# 9xVoice_MikeB_SMD_v1_0.net
KiCad netlist of a schematic drawn in EAGLE
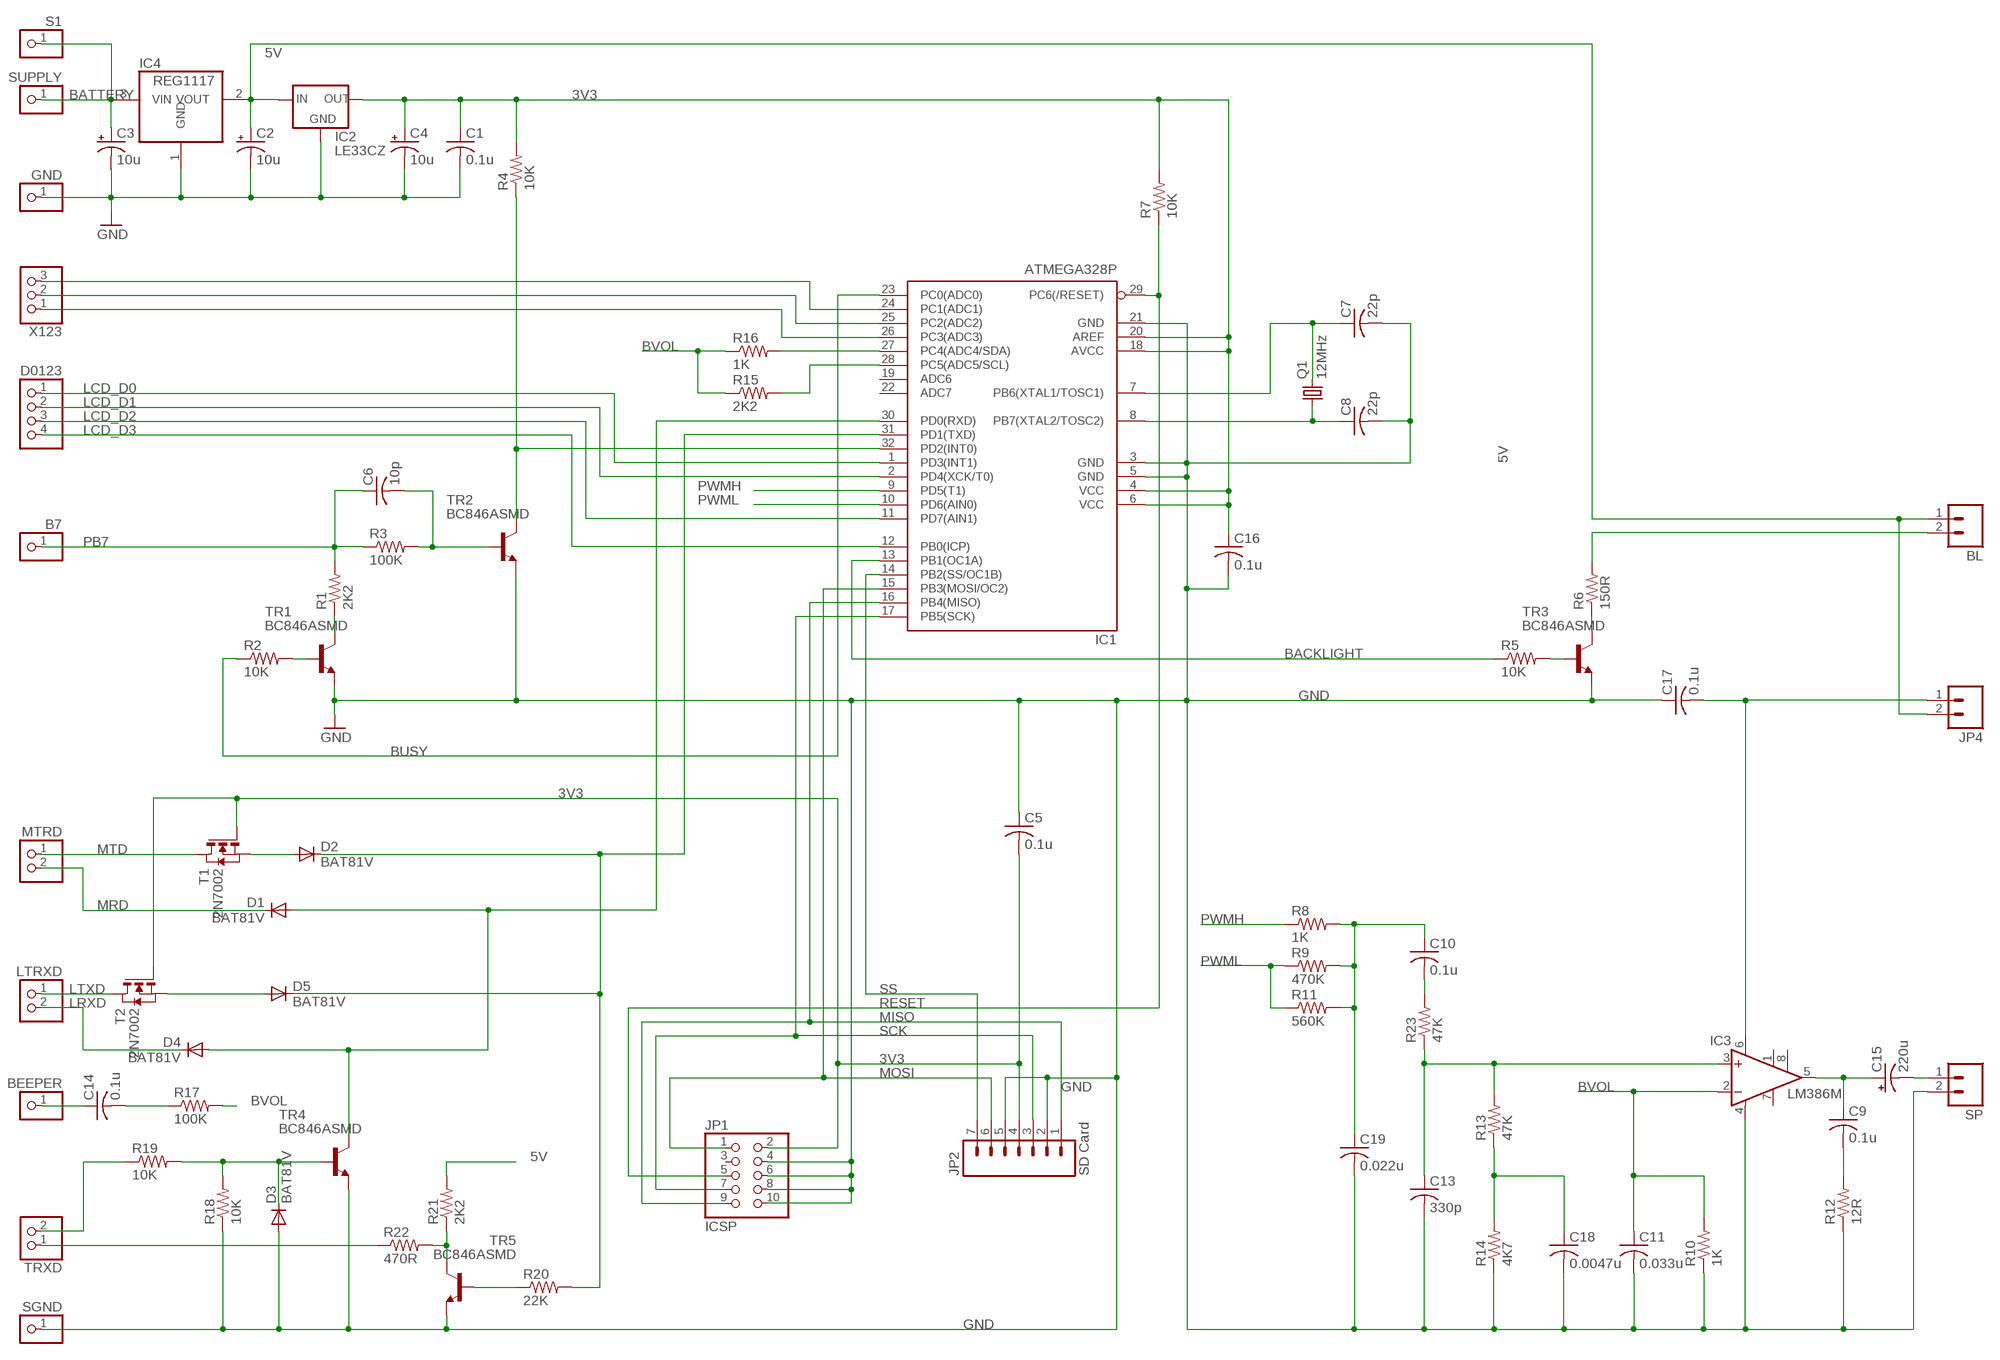
[diagram p0: schematic, sheet 1]

(export (version "E")
  (design (tool "Eeschema 10.0.6"))
  (components
    (comp (ref "B7")
      (value "PINHD-1X1")
      (footprint "eagle-import:1X01")
      (libsource (lib "eagle-import") (part "PINHD-1X1"))
    )
    (comp (ref "BEEPER")
      (value "PINHD-1X1")
      (footprint "eagle-import:1X01")
      (libsource (lib "eagle-import") (part "PINHD-1X1"))
    )
    (comp (ref "BL")
      (value "M02PTH")
      (footprint "eagle-import:1X02")
      (libsource (lib "eagle-import") (part "M02PTH"))
    )
    (comp (ref "C1")
      (value "0.1u")
      (footprint "eagle-import:C1206")
      (libsource (lib "eagle-import") (part "C-USC1206"))
    )
    (comp (ref "C2")
      (value "10u")
      (footprint "eagle-import:A_3216-18R")
      (libsource (lib "eagle-import") (part "CPOL-USA/3216-18R"))
    )
    (comp (ref "C3")
      (value "10u")
      (footprint "eagle-import:A_3216-18R")
      (libsource (lib "eagle-import") (part "CPOL-USA/3216-18R"))
    )
    (comp (ref "C4")
      (value "10u")
      (footprint "eagle-import:A_3216-18R")
      (libsource (lib "eagle-import") (part "CPOL-USA/3216-18R"))
    )
    (comp (ref "C5")
      (value "0.1u")
      (footprint "eagle-import:C1206")
      (libsource (lib "eagle-import") (part "C-USC1206"))
    )
    (comp (ref "C6")
      (value "10p")
      (footprint "eagle-import:C1206")
      (libsource (lib "eagle-import") (part "C-USC1206"))
    )
    (comp (ref "C7")
      (value "22p")
      (footprint "eagle-import:C1206")
      (libsource (lib "eagle-import") (part "C-USC1206"))
    )
    (comp (ref "C8")
      (value "22p")
      (footprint "eagle-import:C1206")
      (libsource (lib "eagle-import") (part "C-USC1206"))
    )
    (comp (ref "C9")
      (value "0.1u")
      (footprint "eagle-import:C1206")
      (libsource (lib "eagle-import") (part "C-USC1206"))
    )
    (comp (ref "C10")
      (value "0.1u")
      (footprint "eagle-import:C1206")
      (libsource (lib "eagle-import") (part "C-USC1206"))
    )
    (comp (ref "C11")
      (value "0.033u")
      (footprint "eagle-import:C1206")
      (libsource (lib "eagle-import") (part "C-USC1206"))
    )
    (comp (ref "C13")
      (value "330p")
      (footprint "eagle-import:C1206")
      (libsource (lib "eagle-import") (part "C-USC1206"))
    )
    (comp (ref "C14")
      (value "0.1u")
      (footprint "eagle-import:C1206")
      (libsource (lib "eagle-import") (part "C-USC1206"))
    )
    (comp (ref "C15")
      (value "220u")
      (footprint "eagle-import:CT7343")
      (libsource (lib "eagle-import") (part "CPOL-USCT7343"))
    )
    (comp (ref "C16")
      (value "0.1u")
      (footprint "eagle-import:C1206")
      (libsource (lib "eagle-import") (part "C-USC1206"))
    )
    (comp (ref "C17")
      (value "0.1u")
      (footprint "eagle-import:C1206")
      (libsource (lib "eagle-import") (part "C-USC1206"))
    )
    (comp (ref "C18")
      (value "0.0047u")
      (footprint "eagle-import:C1206")
      (libsource (lib "eagle-import") (part "C-USC1206"))
    )
    (comp (ref "C19")
      (value "0.022u")
      (footprint "eagle-import:C1206")
      (libsource (lib "eagle-import") (part "C-USC1206"))
    )
    (comp (ref "D1")
      (value "BAT81V")
      (footprint "eagle-import:SOD123")
      (libsource (lib "eagle-import") (part "DIODE-SOD123"))
    )
    (comp (ref "D2")
      (value "BAT81V")
      (footprint "eagle-import:SOD123")
      (libsource (lib "eagle-import") (part "DIODE-SOD123"))
    )
    (comp (ref "D3")
      (value "BAT81V")
      (footprint "eagle-import:SOD123")
      (libsource (lib "eagle-import") (part "DIODE-SOD123"))
    )
    (comp (ref "D4")
      (value "BAT81V")
      (footprint "eagle-import:SOD123")
      (libsource (lib "eagle-import") (part "DIODE-SOD123"))
    )
    (comp (ref "D5")
      (value "BAT81V")
      (footprint "eagle-import:SOD123")
      (libsource (lib "eagle-import") (part "DIODE-SOD123"))
    )
    (comp (ref "D0123")
      (value "PINHD-1X4")
      (footprint "eagle-import:1X04")
      (libsource (lib "eagle-import") (part "PINHD-1X4"))
    )
    (comp (ref "GND")
      (value "PINHD-1X1")
      (footprint "eagle-import:1X01")
      (libsource (lib "eagle-import") (part "PINHD-1X1"))
    )
    (comp (ref "IC1")
      (value "ATMEGA328P")
      (footprint "eagle-import:TQFP32-08")
      (fields
        (field (name "MPN") "ATMEGA8-16AU")
        (field (name "MPN_1") "ATMEGA8-16AU")
        (field (name "OC_FARNELL") "9171371")
        (field (name "OC_NEWARK") "73M8863")
      )
      (libsource (lib "eagle-import") (part "MEGA8-AI"))
    )
    (comp (ref "IC2")
      (value "LE33CZ")
      (footprint "eagle-import:SOT23")
      (libsource (lib "eagle-import") (part "XC63FPM"))
    )
    (comp (ref "IC3")
      (value "LM386M")
      (footprint "eagle-import:SO08")
      (libsource (lib "eagle-import") (part "LM386?-M1"))
    )
    (comp (ref "IC4")
      (value "REG1117")
      (footprint "eagle-import:SOT223")
      (libsource (lib "eagle-import") (part "REG1117"))
    )
    (comp (ref "JP1")
      (value "ICSP")
      (footprint "eagle-import:2X05")
      (libsource (lib "eagle-import") (part "PINHD-2X5"))
    )
    (comp (ref "JP2")
      (value "SD Card")
      (footprint "eagle-import:1X07")
      (libsource (lib "eagle-import") (part "M07"))
    )
    (comp (ref "JP4")
      (value "M02PTH")
      (footprint "eagle-import:1X02")
      (libsource (lib "eagle-import") (part "M02PTH"))
    )
    (comp (ref "LTRXD")
      (value "PINHD-1X2")
      (footprint "eagle-import:1X02")
      (libsource (lib "eagle-import") (part "PINHD-1X2"))
    )
    (comp (ref "MTRD")
      (value "PINHD-1X2")
      (footprint "eagle-import:1X02")
      (libsource (lib "eagle-import") (part "PINHD-1X2"))
    )
    (comp (ref "Q1")
      (value "12MHz")
      (footprint "eagle-import:2-SMD")
      (libsource (lib "eagle-import") (part "7A"))
    )
    (comp (ref "R1")
      (value "2K2")
      (footprint "eagle-import:R1206")
      (libsource (lib "eagle-import") (part "R-US_R1206"))
    )
    (comp (ref "R2")
      (value "10K")
      (footprint "eagle-import:R1206")
      (libsource (lib "eagle-import") (part "R-US_R1206"))
    )
    (comp (ref "R3")
      (value "100K")
      (footprint "eagle-import:R1206")
      (libsource (lib "eagle-import") (part "R-US_R1206"))
    )
    (comp (ref "R4")
      (value "10K")
      (footprint "eagle-import:R1206")
      (libsource (lib "eagle-import") (part "R-US_R1206"))
    )
    (comp (ref "R5")
      (value "10K")
      (footprint "eagle-import:R1206")
      (libsource (lib "eagle-import") (part "R-US_R1206"))
    )
    (comp (ref "R6")
      (value "150R")
      (footprint "eagle-import:R1206")
      (libsource (lib "eagle-import") (part "R-US_R1206"))
    )
    (comp (ref "R7")
      (value "10K")
      (footprint "eagle-import:R1206")
      (libsource (lib "eagle-import") (part "R-US_R1206"))
    )
    (comp (ref "R8")
      (value "1K")
      (footprint "eagle-import:R1206")
      (libsource (lib "eagle-import") (part "R-US_R1206"))
    )
    (comp (ref "R9")
      (value "470K")
      (footprint "eagle-import:R1206")
      (libsource (lib "eagle-import") (part "R-US_R1206"))
    )
    (comp (ref "R10")
      (value "1K")
      (footprint "eagle-import:R1206")
      (libsource (lib "eagle-import") (part "R-US_R1206"))
    )
    (comp (ref "R11")
      (value "560K")
      (footprint "eagle-import:R1206")
      (libsource (lib "eagle-import") (part "R-US_R1206"))
    )
    (comp (ref "R12")
      (value "12R")
      (footprint "eagle-import:R1206")
      (libsource (lib "eagle-import") (part "R-US_R1206"))
    )
    (comp (ref "R13")
      (value "47K")
      (footprint "eagle-import:R1206")
      (libsource (lib "eagle-import") (part "R-US_R1206"))
    )
    (comp (ref "R14")
      (value "4K7")
      (footprint "eagle-import:R1206")
      (libsource (lib "eagle-import") (part "R-US_R1206"))
    )
    (comp (ref "R15")
      (value "2K2")
      (footprint "eagle-import:R1206")
      (libsource (lib "eagle-import") (part "R-US_R1206"))
    )
    (comp (ref "R16")
      (value "1K")
      (footprint "eagle-import:R1206")
      (libsource (lib "eagle-import") (part "R-US_R1206"))
    )
    (comp (ref "R17")
      (value "100K")
      (footprint "eagle-import:R1206")
      (libsource (lib "eagle-import") (part "R-US_R1206"))
    )
    (comp (ref "R18")
      (value "10K")
      (footprint "eagle-import:R1206")
      (libsource (lib "eagle-import") (part "R-US_R1206"))
    )
    (comp (ref "R19")
      (value "10K")
      (footprint "eagle-import:R1206")
      (libsource (lib "eagle-import") (part "R-US_R1206"))
    )
    (comp (ref "R20")
      (value "22K")
      (footprint "eagle-import:R1206")
      (libsource (lib "eagle-import") (part "R-US_R1206"))
    )
    (comp (ref "R21")
      (value "2K2")
      (footprint "eagle-import:R1206")
      (libsource (lib "eagle-import") (part "R-US_R1206"))
    )
    (comp (ref "R22")
      (value "470R")
      (footprint "eagle-import:R1206")
      (libsource (lib "eagle-import") (part "R-US_R1206"))
    )
    (comp (ref "R23")
      (value "47K")
      (footprint "eagle-import:R1206")
      (libsource (lib "eagle-import") (part "R-US_R1206"))
    )
    (comp (ref "S1")
      (value "PINHD-1X1")
      (footprint "eagle-import:1X01")
      (libsource (lib "eagle-import") (part "PINHD-1X1"))
    )
    (comp (ref "SGND")
      (value "PINHD-1X1")
      (footprint "eagle-import:1X01")
      (libsource (lib "eagle-import") (part "PINHD-1X1"))
    )
    (comp (ref "SP")
      (value "M02PTH")
      (footprint "eagle-import:1X02")
      (libsource (lib "eagle-import") (part "M02PTH"))
    )
    (comp (ref "SUPPLY")
      (value "PINHD-1X1")
      (footprint "eagle-import:1X01")
      (libsource (lib "eagle-import") (part "PINHD-1X1"))
    )
    (comp (ref "T1")
      (value "2N7002")
      (footprint "eagle-import:SOT-23")
      (libsource (lib "eagle-import") (part "NMOSSOT23"))
    )
    (comp (ref "T2")
      (value "2N7002")
      (footprint "eagle-import:SOT-23")
      (libsource (lib "eagle-import") (part "NMOSSOT23"))
    )
    (comp (ref "TR1")
      (value "BC846ASMD")
      (footprint "eagle-import:SOT23")
      (libsource (lib "eagle-import") (part "BC846SMDA"))
    )
    (comp (ref "TR2")
      (value "BC846ASMD")
      (footprint "eagle-import:SOT23")
      (libsource (lib "eagle-import") (part "BC846SMDA"))
    )
    (comp (ref "TR3")
      (value "BC846ASMD")
      (footprint "eagle-import:SOT23")
      (libsource (lib "eagle-import") (part "BC846SMDA"))
    )
    (comp (ref "TR4")
      (value "BC846ASMD")
      (footprint "eagle-import:SOT23")
      (libsource (lib "eagle-import") (part "BC846SMDA"))
    )
    (comp (ref "TR5")
      (value "BC846ASMD")
      (footprint "eagle-import:SOT23")
      (libsource (lib "eagle-import") (part "BC846SMDA"))
    )
    (comp (ref "TRXD")
      (value "PINHD-1X2")
      (footprint "eagle-import:1X02")
      (libsource (lib "eagle-import") (part "PINHD-1X2"))
    )
    (comp (ref "X123")
      (value "PINHD-1X3")
      (footprint "eagle-import:1X03")
      (libsource (lib "eagle-import") (part "PINHD-1X3"))
    )
  )
  (nets
    (net (code "1") (name "/3V3") (class "Default")
      (node (ref "C1") (pin "1") (pinfunction "1_1") (pintype "passive"))
      (node (ref "C16") (pin "1") (pinfunction "1_1") (pintype "passive"))
      (node (ref "C4") (pin "+") (pinfunction "+_+") (pintype "passive"))
      (node (ref "C5") (pin "2") (pinfunction "2_2") (pintype "passive"))
      (node (ref "IC1") (pin "18") (pinfunction "AVCC_18") (pintype "power_in"))
      (node (ref "IC1") (pin "20") (pinfunction "AREF_20") (pintype "passive"))
      (node (ref "IC1") (pin "4") (pinfunction "VCC_4") (pintype "power_in"))
      (node (ref "IC1") (pin "6") (pinfunction "VCC_6") (pintype "power_in"))
      (node (ref "IC2") (pin "2") (pinfunction "OUT_2") (pintype "passive"))
      (node (ref "JP1") (pin "2") (pinfunction "2_2") (pintype "passive"))
      (node (ref "JP2") (pin "4") (pinfunction "4_4") (pintype "passive"))
      (node (ref "R4") (pin "2") (pinfunction "2_2") (pintype "passive"))
      (node (ref "R7") (pin "2") (pinfunction "2_2") (pintype "passive"))
      (node (ref "T1") (pin "3") (pinfunction "G_3") (pintype "passive"))
      (node (ref "T2") (pin "3") (pinfunction "G_3") (pintype "passive"))
    )
    (net (code "2") (name "/5V") (class "Default")
      (node (ref "BL") (pin "1") (pinfunction "1_1") (pintype "passive"))
      (node (ref "C2") (pin "+") (pinfunction "+_+") (pintype "passive"))
      (node (ref "IC2") (pin "3") (pinfunction "IN_3") (pintype "input"))
      (node (ref "IC4") (pin "2") (pinfunction "VOUT_2") (pintype "output"))
      (node (ref "JP4") (pin "2") (pinfunction "2_2") (pintype "passive"))
      (node (ref "R21") (pin "2") (pinfunction "2_2") (pintype "passive"))
    )
    (net (code "3") (name "/BACKLIGHT") (class "Default")
      (node (ref "IC1") (pin "13") (pinfunction "PB1(OC1A)_13") (pintype "bidirectional"))
      (node (ref "R5") (pin "1") (pinfunction "1_1") (pintype "passive"))
    )
    (net (code "4") (name "/BATTERY") (class "Default")
      (node (ref "C3") (pin "+") (pinfunction "+_+") (pintype "passive"))
      (node (ref "IC4") (pin "3") (pinfunction "VIN_3") (pintype "input"))
      (node (ref "S1") (pin "1") (pinfunction "1_1") (pintype "passive"))
      (node (ref "SUPPLY") (pin "1") (pinfunction "1_1") (pintype "passive"))
    )
    (net (code "5") (name "/BUSY") (class "Default")
      (node (ref "IC1") (pin "23") (pinfunction "PC0(ADC0)_23") (pintype "bidirectional"))
      (node (ref "R2") (pin "1") (pinfunction "1_1") (pintype "passive"))
    )
    (net (code "6") (name "/BVOL") (class "Default")
      (node (ref "C11") (pin "1") (pinfunction "1_1") (pintype "passive"))
      (node (ref "IC3") (pin "2") (pinfunction "-IN_2") (pintype "input"))
      (node (ref "R10") (pin "2") (pinfunction "2_2") (pintype "passive"))
      (node (ref "R15") (pin "1") (pinfunction "1_1") (pintype "passive"))
      (node (ref "R16") (pin "1") (pinfunction "1_1") (pintype "passive"))
      (node (ref "R17") (pin "2") (pinfunction "2_2") (pintype "passive"))
    )
    (net (code "7") (name "/LCD_D0") (class "Default")
      (node (ref "D0123") (pin "1") (pinfunction "1_1") (pintype "passive"))
      (node (ref "IC1") (pin "1") (pinfunction "PD3(INT1)_1") (pintype "bidirectional"))
    )
    (net (code "8") (name "/LCD_D1") (class "Default")
      (node (ref "D0123") (pin "2") (pinfunction "2_2") (pintype "passive"))
      (node (ref "IC1") (pin "2") (pinfunction "PD4(XCK/T0)_2") (pintype "bidirectional"))
    )
    (net (code "9") (name "/LCD_D2") (class "Default")
      (node (ref "D0123") (pin "3") (pinfunction "3_3") (pintype "passive"))
      (node (ref "IC1") (pin "11") (pinfunction "PD7(AIN1)_11") (pintype "bidirectional"))
    )
    (net (code "10") (name "/LCD_D3") (class "Default")
      (node (ref "D0123") (pin "4") (pinfunction "4_4") (pintype "passive"))
      (node (ref "IC1") (pin "12") (pinfunction "PB0(ICP)_12") (pintype "bidirectional"))
    )
    (net (code "11") (name "/LRXD") (class "Default")
      (node (ref "D4") (pin "C") (pinfunction "C_C") (pintype "passive"))
      (node (ref "LTRXD") (pin "2") (pinfunction "2_2") (pintype "passive"))
    )
    (net (code "12") (name "/LTXD") (class "Default")
      (node (ref "LTRXD") (pin "1") (pinfunction "1_1") (pintype "passive"))
      (node (ref "T2") (pin "1") (pinfunction "D_1") (pintype "passive"))
    )
    (net (code "13") (name "/MISO") (class "Default")
      (node (ref "IC1") (pin "16") (pinfunction "PB4(MISO)_16") (pintype "bidirectional"))
      (node (ref "JP1") (pin "9") (pinfunction "9_9") (pintype "passive"))
      (node (ref "JP2") (pin "1") (pinfunction "1_1") (pintype "passive"))
    )
    (net (code "14") (name "/MOSI") (class "Default")
      (node (ref "IC1") (pin "15") (pinfunction "PB3(MOSI/OC2)_15") (pintype "bidirectional"))
      (node (ref "JP1") (pin "1") (pinfunction "1_1") (pintype "passive"))
      (node (ref "JP2") (pin "6") (pinfunction "6_6") (pintype "passive"))
    )
    (net (code "15") (name "/MRD") (class "Default")
      (node (ref "D1") (pin "C") (pinfunction "C_C") (pintype "passive"))
      (node (ref "MTRD") (pin "2") (pinfunction "2_2") (pintype "passive"))
    )
    (net (code "16") (name "/MTD") (class "Default")
      (node (ref "MTRD") (pin "1") (pinfunction "1_1") (pintype "passive"))
      (node (ref "T1") (pin "1") (pinfunction "D_1") (pintype "passive"))
    )
    (net (code "17") (name "/PB7") (class "Default")
      (node (ref "B7") (pin "1") (pinfunction "1_1") (pintype "passive"))
      (node (ref "C6") (pin "1") (pinfunction "1_1") (pintype "passive"))
      (node (ref "R1") (pin "2") (pinfunction "2_2") (pintype "passive"))
      (node (ref "R3") (pin "1") (pinfunction "1_1") (pintype "passive"))
    )
    (net (code "18") (name "/PWMH") (class "Default")
      (node (ref "IC1") (pin "9") (pinfunction "PD5(T1)_9") (pintype "bidirectional"))
      (node (ref "R8") (pin "1") (pinfunction "1_1") (pintype "passive"))
    )
    (net (code "19") (name "/PWML") (class "Default")
      (node (ref "IC1") (pin "10") (pinfunction "PD6(AIN0)_10") (pintype "bidirectional"))
      (node (ref "R11") (pin "1") (pinfunction "1_1") (pintype "passive"))
      (node (ref "R9") (pin "1") (pinfunction "1_1") (pintype "passive"))
    )
    (net (code "20") (name "/RESET") (class "Default")
      (node (ref "IC1") (pin "29") (pinfunction "PC6(/RESET)_29") (pintype "bidirectional"))
      (node (ref "JP1") (pin "5") (pinfunction "5_5") (pintype "passive"))
      (node (ref "R7") (pin "1") (pinfunction "1_1") (pintype "passive"))
    )
    (net (code "21") (name "/SCK") (class "Default")
      (node (ref "IC1") (pin "17") (pinfunction "PB5(SCK)_17") (pintype "bidirectional"))
      (node (ref "JP1") (pin "7") (pinfunction "7_7") (pintype "passive"))
      (node (ref "JP2") (pin "3") (pinfunction "3_3") (pintype "passive"))
    )
    (net (code "22") (name "/SS") (class "Default")
      (node (ref "IC1") (pin "14") (pinfunction "PB2(SS/OC1B)_14") (pintype "bidirectional"))
      (node (ref "JP2") (pin "7") (pinfunction "7_7") (pintype "passive"))
    )
    (net (code "23") (name "GND") (class "Default")
      (node (ref "C1") (pin "2") (pinfunction "2_2") (pintype "passive"))
      (node (ref "C11") (pin "2") (pinfunction "2_2") (pintype "passive"))
      (node (ref "C13") (pin "2") (pinfunction "2_2") (pintype "passive"))
      (node (ref "C16") (pin "2") (pinfunction "2_2") (pintype "passive"))
      (node (ref "C17") (pin "1") (pinfunction "1_1") (pintype "passive"))
      (node (ref "C18") (pin "2") (pinfunction "2_2") (pintype "passive"))
      (node (ref "C19") (pin "2") (pinfunction "2_2") (pintype "passive"))
      (node (ref "C2") (pin "-") (pinfunction "-_-") (pintype "passive"))
      (node (ref "C3") (pin "-") (pinfunction "-_-") (pintype "passive"))
      (node (ref "C4") (pin "-") (pinfunction "-_-") (pintype "passive"))
      (node (ref "C5") (pin "1") (pinfunction "1_1") (pintype "passive"))
      (node (ref "C7") (pin "2") (pinfunction "2_2") (pintype "passive"))
      (node (ref "C8") (pin "2") (pinfunction "2_2") (pintype "passive"))
      (node (ref "D3") (pin "A") (pinfunction "A_A") (pintype "passive"))
      (node (ref "GND") (pin "1") (pinfunction "1_1") (pintype "passive"))
      (node (ref "IC1") (pin "21") (pinfunction "GND_21") (pintype "power_in"))
      (node (ref "IC1") (pin "3") (pinfunction "GND_3") (pintype "power_in"))
      (node (ref "IC1") (pin "5") (pinfunction "GND_5") (pintype "power_in"))
      (node (ref "IC2") (pin "1") (pinfunction "GND_1") (pintype "input"))
      (node (ref "IC3") (pin "4") (pinfunction "GND_4") (pintype "power_in"))
      (node (ref "IC4") (pin "1") (pinfunction "GND_1") (pintype "power_in"))
      (node (ref "JP1") (pin "10") (pinfunction "10_10") (pintype "passive"))
      (node (ref "JP1") (pin "4") (pinfunction "4_4") (pintype "passive"))
      (node (ref "JP1") (pin "6") (pinfunction "6_6") (pintype "passive"))
      (node (ref "JP1") (pin "8") (pinfunction "8_8") (pintype "passive"))
      (node (ref "JP2") (pin "2") (pinfunction "2_2") (pintype "passive"))
      (node (ref "JP2") (pin "5") (pinfunction "5_5") (pintype "passive"))
      (node (ref "R10") (pin "1") (pinfunction "1_1") (pintype "passive"))
      (node (ref "R12") (pin "1") (pinfunction "1_1") (pintype "passive"))
      (node (ref "R14") (pin "1") (pinfunction "1_1") (pintype "passive"))
      (node (ref "R18") (pin "1") (pinfunction "1_1") (pintype "passive"))
      (node (ref "SGND") (pin "1") (pinfunction "1_1") (pintype "passive"))
      (node (ref "SP") (pin "2") (pinfunction "2_2") (pintype "passive"))
      (node (ref "TR1") (pin "2") (pinfunction "E_2") (pintype "passive"))
      (node (ref "TR2") (pin "2") (pinfunction "E_2") (pintype "passive"))
      (node (ref "TR3") (pin "2") (pinfunction "E_2") (pintype "passive"))
      (node (ref "TR4") (pin "2") (pinfunction "E_2") (pintype "passive"))
      (node (ref "TR5") (pin "2") (pinfunction "E_2") (pintype "passive"))
    )
    (net (code "24") (name "Net-(BEEPER-Pad1)") (class "Default")
      (node (ref "BEEPER") (pin "1") (pinfunction "1_1") (pintype "passive"))
      (node (ref "C14") (pin "1") (pinfunction "1_1") (pintype "passive"))
    )
    (net (code "25") (name "Net-(BL-Pad2)") (class "Default")
      (node (ref "BL") (pin "2") (pinfunction "2_2") (pintype "passive"))
      (node (ref "R6") (pin "2") (pinfunction "2_2") (pintype "passive"))
    )
    (net (code "26") (name "Net-(C9-Pad2)") (class "Default")
      (node (ref "C9") (pin "2") (pinfunction "2_2") (pintype "passive"))
      (node (ref "R12") (pin "2") (pinfunction "2_2") (pintype "passive"))
    )
    (net (code "27") (name "Net-(C10-Pad1)") (class "Default")
      (node (ref "C10") (pin "1") (pinfunction "1_1") (pintype "passive"))
      (node (ref "C19") (pin "1") (pinfunction "1_1") (pintype "passive"))
      (node (ref "R11") (pin "2") (pinfunction "2_2") (pintype "passive"))
      (node (ref "R8") (pin "2") (pinfunction "2_2") (pintype "passive"))
      (node (ref "R9") (pin "2") (pinfunction "2_2") (pintype "passive"))
    )
    (net (code "28") (name "Net-(C10-Pad2)") (class "Default")
      (node (ref "C10") (pin "2") (pinfunction "2_2") (pintype "passive"))
      (node (ref "R23") (pin "2") (pinfunction "2_2") (pintype "passive"))
    )
    (net (code "29") (name "Net-(C14-Pad2)") (class "Default")
      (node (ref "C14") (pin "2") (pinfunction "2_2") (pintype "passive"))
      (node (ref "R17") (pin "1") (pinfunction "1_1") (pintype "passive"))
    )
    (net (code "30") (name "Net-(C15-Pad-)") (class "Default")
      (node (ref "C15") (pin "-") (pinfunction "-_-") (pintype "passive"))
      (node (ref "SP") (pin "1") (pinfunction "1_1") (pintype "passive"))
    )
    (net (code "31") (name "Net-(C18-Pad1)") (class "Default")
      (node (ref "C18") (pin "1") (pinfunction "1_1") (pintype "passive"))
      (node (ref "R13") (pin "1") (pinfunction "1_1") (pintype "passive"))
      (node (ref "R14") (pin "2") (pinfunction "2_2") (pintype "passive"))
    )
    (net (code "32") (name "Net-(IC1-PB6(XTAL1{slash}TOSC1))") (class "Default")
      (node (ref "C7") (pin "1") (pinfunction "1_1") (pintype "passive"))
      (node (ref "IC1") (pin "7") (pinfunction "PB6(XTAL1/TOSC1)_7") (pintype "bidirectional"))
      (node (ref "Q1") (pin "P$2") (pinfunction "2_P$2") (pintype "passive"))
    )
    (net (code "33") (name "Net-(IC1-PB7(XTAL2{slash}TOSC2))") (class "Default")
      (node (ref "C8") (pin "1") (pinfunction "1_1") (pintype "passive"))
      (node (ref "IC1") (pin "8") (pinfunction "PB7(XTAL2/TOSC2)_8") (pintype "bidirectional"))
      (node (ref "Q1") (pin "P$1") (pinfunction "1_P$1") (pintype "passive"))
    )
    (net (code "34") (name "Net-(IC1-PC1(ADC1))") (class "Default")
      (node (ref "IC1") (pin "24") (pinfunction "PC1(ADC1)_24") (pintype "bidirectional"))
      (node (ref "X123") (pin "3") (pinfunction "3_3") (pintype "passive"))
    )
    (net (code "35") (name "Net-(IC1-PC2(ADC2))") (class "Default")
      (node (ref "IC1") (pin "25") (pinfunction "PC2(ADC2)_25") (pintype "bidirectional"))
      (node (ref "X123") (pin "2") (pinfunction "2_2") (pintype "passive"))
    )
    (net (code "36") (name "Net-(IC1-PC3(ADC3))") (class "Default")
      (node (ref "IC1") (pin "26") (pinfunction "PC3(ADC3)_26") (pintype "bidirectional"))
      (node (ref "X123") (pin "1") (pinfunction "1_1") (pintype "passive"))
    )
    (net (code "37") (name "Net-(IC1-PC4(ADC4{slash}SDA))") (class "Default")
      (node (ref "IC1") (pin "27") (pinfunction "PC4(ADC4/SDA)_27") (pintype "bidirectional"))
      (node (ref "R16") (pin "2") (pinfunction "2_2") (pintype "passive"))
    )
    (net (code "38") (name "Net-(IC1-PC5(ADC5{slash}SCL))") (class "Default")
      (node (ref "IC1") (pin "28") (pinfunction "PC5(ADC5/SCL)_28") (pintype "bidirectional"))
      (node (ref "R15") (pin "2") (pinfunction "2_2") (pintype "passive"))
    )
    (net (code "39") (name "Net-(IC1-PD0(RXD))") (class "Default")
      (node (ref "D1") (pin "A") (pinfunction "A_A") (pintype "passive"))
      (node (ref "D4") (pin "A") (pinfunction "A_A") (pintype "passive"))
      (node (ref "IC1") (pin "30") (pinfunction "PD0(RXD)_30") (pintype "bidirectional"))
      (node (ref "TR4") (pin "3") (pinfunction "C_3") (pintype "passive"))
    )
    (net (code "40") (name "Net-(IC1-PD1(TXD))") (class "Default")
      (node (ref "D2") (pin "C") (pinfunction "C_C") (pintype "passive"))
      (node (ref "D5") (pin "C") (pinfunction "C_C") (pintype "passive"))
      (node (ref "IC1") (pin "31") (pinfunction "PD1(TXD)_31") (pintype "bidirectional"))
      (node (ref "R20") (pin "2") (pinfunction "2_2") (pintype "passive"))
    )
    (net (code "41") (name "Net-(IC1-PD2(INT0))") (class "Default")
      (node (ref "IC1") (pin "32") (pinfunction "PD2(INT0)_32") (pintype "bidirectional"))
      (node (ref "R4") (pin "1") (pinfunction "1_1") (pintype "passive"))
      (node (ref "TR2") (pin "3") (pinfunction "C_3") (pintype "passive"))
    )
    (net (code "42") (name "Net-(IC3-+IN)") (class "Default")
      (node (ref "C13") (pin "1") (pinfunction "1_1") (pintype "passive"))
      (node (ref "IC3") (pin "3") (pinfunction "+IN_3") (pintype "input"))
      (node (ref "R13") (pin "2") (pinfunction "2_2") (pintype "passive"))
      (node (ref "R23") (pin "1") (pinfunction "1_1") (pintype "passive"))
    )
    (net (code "43") (name "Net-(IC3-OUT)") (class "Default")
      (node (ref "C15") (pin "+") (pinfunction "+_+") (pintype "passive"))
      (node (ref "C9") (pin "1") (pinfunction "1_1") (pintype "passive"))
      (node (ref "IC3") (pin "5") (pinfunction "OUT_5") (pintype "output"))
    )
    (net (code "44") (name "Net-(IC3-VS)") (class "Default")
      (node (ref "C17") (pin "2") (pinfunction "2_2") (pintype "passive"))
      (node (ref "IC3") (pin "6") (pinfunction "VS_6") (pintype "power_in"))
      (node (ref "JP4") (pin "1") (pinfunction "1_1") (pintype "passive"))
    )
    (net (code "45") (name "Net-(R19-Pad1)") (class "Default")
      (node (ref "R19") (pin "1") (pinfunction "1_1") (pintype "passive"))
      (node (ref "TRXD") (pin "2") (pinfunction "2_2") (pintype "passive"))
    )
    (net (code "46") (name "Net-(R22-Pad1)") (class "Default")
      (node (ref "R22") (pin "1") (pinfunction "1_1") (pintype "passive"))
      (node (ref "TRXD") (pin "1") (pinfunction "1_1") (pintype "passive"))
    )
    (net (code "47") (name "Net-(T1-S)") (class "Default")
      (node (ref "D2") (pin "A") (pinfunction "A_A") (pintype "passive"))
      (node (ref "T1") (pin "2") (pinfunction "S_2") (pintype "passive"))
    )
    (net (code "48") (name "Net-(T2-S)") (class "Default")
      (node (ref "D5") (pin "A") (pinfunction "A_A") (pintype "passive"))
      (node (ref "T2") (pin "2") (pinfunction "S_2") (pintype "passive"))
    )
    (net (code "49") (name "Net-(TR1-B)") (class "Default")
      (node (ref "R2") (pin "2") (pinfunction "2_2") (pintype "passive"))
      (node (ref "TR1") (pin "1") (pinfunction "B_1") (pintype "passive"))
    )
    (net (code "50") (name "Net-(TR1-C)") (class "Default")
      (node (ref "R1") (pin "1") (pinfunction "1_1") (pintype "passive"))
      (node (ref "TR1") (pin "3") (pinfunction "C_3") (pintype "passive"))
    )
    (net (code "51") (name "Net-(TR2-B)") (class "Default")
      (node (ref "C6") (pin "2") (pinfunction "2_2") (pintype "passive"))
      (node (ref "R3") (pin "2") (pinfunction "2_2") (pintype "passive"))
      (node (ref "TR2") (pin "1") (pinfunction "B_1") (pintype "passive"))
    )
    (net (code "52") (name "Net-(TR3-B)") (class "Default")
      (node (ref "R5") (pin "2") (pinfunction "2_2") (pintype "passive"))
      (node (ref "TR3") (pin "1") (pinfunction "B_1") (pintype "passive"))
    )
    (net (code "53") (name "Net-(TR3-C)") (class "Default")
      (node (ref "R6") (pin "1") (pinfunction "1_1") (pintype "passive"))
      (node (ref "TR3") (pin "3") (pinfunction "C_3") (pintype "passive"))
    )
    (net (code "54") (name "Net-(TR4-B)") (class "Default")
      (node (ref "D3") (pin "C") (pinfunction "C_C") (pintype "passive"))
      (node (ref "R18") (pin "2") (pinfunction "2_2") (pintype "passive"))
      (node (ref "R19") (pin "2") (pinfunction "2_2") (pintype "passive"))
      (node (ref "TR4") (pin "1") (pinfunction "B_1") (pintype "passive"))
    )
    (net (code "55") (name "Net-(TR5-B)") (class "Default")
      (node (ref "R20") (pin "1") (pinfunction "1_1") (pintype "passive"))
      (node (ref "TR5") (pin "1") (pinfunction "B_1") (pintype "passive"))
    )
    (net (code "56") (name "Net-(TR5-C)") (class "Default")
      (node (ref "R21") (pin "1") (pinfunction "1_1") (pintype "passive"))
      (node (ref "R22") (pin "2") (pinfunction "2_2") (pintype "passive"))
      (node (ref "TR5") (pin "3") (pinfunction "C_3") (pintype "passive"))
    )
    (net (code "57") (name "unconnected-(IC1-ADC6-Pad19)") (class "Default")
      (node (ref "IC1") (pin "19") (pinfunction "ADC6_19") (pintype "bidirectional"))
    )
    (net (code "58") (name "unconnected-(IC1-ADC7-Pad22)") (class "Default")
      (node (ref "IC1") (pin "22") (pinfunction "ADC7_22") (pintype "bidirectional"))
    )
    (net (code "59") (name "unconnected-(IC3-BYPASS-Pad7)") (class "Default")
      (node (ref "IC3") (pin "7") (pinfunction "BYPASS_7") (pintype "passive"))
    )
    (net (code "60") (name "unconnected-(IC3-GAIN-Pad1)") (class "Default")
      (node (ref "IC3") (pin "1") (pinfunction "GAIN_1") (pintype "passive"))
    )
    (net (code "61") (name "unconnected-(IC3-GAIN-Pad8)") (class "Default")
      (node (ref "IC3") (pin "8") (pinfunction "GAIN_8") (pintype "passive"))
    )
    (net (code "62") (name "unconnected-(JP1-Pad3)") (class "Default")
      (node (ref "JP1") (pin "3") (pinfunction "3_3") (pintype "passive"))
    )
  )
)
